# reptolamp.net
KiCad netlist of a schematic drawn in EAGLE
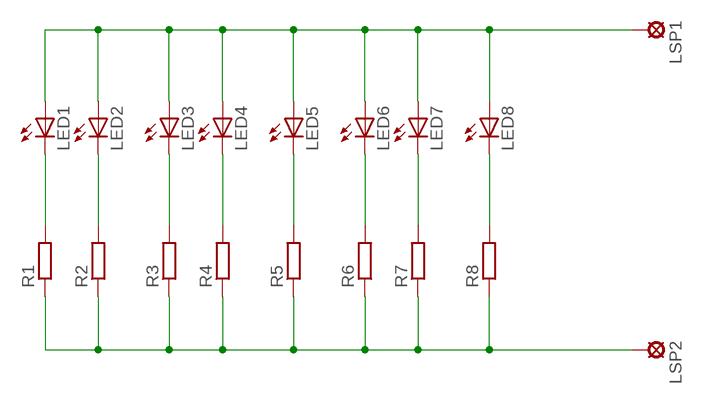
[diagram p0: schematic, sheet 1]

(export (version "E")
  (design (tool "Eeschema 10.0.6"))
  (components
    (comp (ref "LED1")
      (value "LED5MM")
      (footprint "eagle-import:LED5MM")
      (libsource (lib "eagle-import") (part "LED5MM"))
    )
    (comp (ref "LED2")
      (value "LED5MM")
      (footprint "eagle-import:LED5MM")
      (libsource (lib "eagle-import") (part "LED5MM"))
    )
    (comp (ref "LED3")
      (value "LED5MM")
      (footprint "eagle-import:LED5MM")
      (libsource (lib "eagle-import") (part "LED5MM"))
    )
    (comp (ref "LED4")
      (value "LED5MM")
      (footprint "eagle-import:LED5MM")
      (libsource (lib "eagle-import") (part "LED5MM"))
    )
    (comp (ref "LED5")
      (value "LED5MM")
      (footprint "eagle-import:LED5MM")
      (libsource (lib "eagle-import") (part "LED5MM"))
    )
    (comp (ref "LED6")
      (value "LED5MM")
      (footprint "eagle-import:LED5MM")
      (libsource (lib "eagle-import") (part "LED5MM"))
    )
    (comp (ref "LED7")
      (value "LED5MM")
      (footprint "eagle-import:LED5MM")
      (libsource (lib "eagle-import") (part "LED5MM"))
    )
    (comp (ref "LED8")
      (value "LED5MM")
      (footprint "eagle-import:LED5MM")
      (libsource (lib "eagle-import") (part "LED5MM"))
    )
    (comp (ref "LSP1")
      (value "LSP10")
      (footprint "eagle-import:LSP10")
      (libsource (lib "eagle-import") (part "LSP10"))
    )
    (comp (ref "LSP2")
      (value "LSP10")
      (footprint "eagle-import:LSP10")
      (libsource (lib "eagle-import") (part "LSP10"))
    )
    (comp (ref "R1")
      (value "R-EU_0207/10")
      (footprint "eagle-import:0207_10")
      (libsource (lib "eagle-import") (part "R-EU_0207/10"))
    )
    (comp (ref "R2")
      (value "R-EU_0207/10")
      (footprint "eagle-import:0207_10")
      (libsource (lib "eagle-import") (part "R-EU_0207/10"))
    )
    (comp (ref "R3")
      (value "R-EU_0207/10")
      (footprint "eagle-import:0207_10")
      (libsource (lib "eagle-import") (part "R-EU_0207/10"))
    )
    (comp (ref "R4")
      (value "R-EU_0207/10")
      (footprint "eagle-import:0207_10")
      (libsource (lib "eagle-import") (part "R-EU_0207/10"))
    )
    (comp (ref "R5")
      (value "R-EU_0207/10")
      (footprint "eagle-import:0207_10")
      (libsource (lib "eagle-import") (part "R-EU_0207/10"))
    )
    (comp (ref "R6")
      (value "R-EU_0207/10")
      (footprint "eagle-import:0207_10")
      (libsource (lib "eagle-import") (part "R-EU_0207/10"))
    )
    (comp (ref "R7")
      (value "R-EU_0207/10")
      (footprint "eagle-import:0207_10")
      (libsource (lib "eagle-import") (part "R-EU_0207/10"))
    )
    (comp (ref "R8")
      (value "R-EU_0207/10")
      (footprint "eagle-import:0207_10")
      (libsource (lib "eagle-import") (part "R-EU_0207/10"))
    )
  )
  (nets
    (net (code "1") (name "Net-(LED1-C)") (class "Default")
      (node (ref "LED1") (pin "K") (pinfunction "C_K") (pintype "passive"))
      (node (ref "R1") (pin "2") (pinfunction "2_2") (pintype "passive"))
    )
    (net (code "2") (name "Net-(LED1-PadA)") (class "Default")
      (node (ref "LED1") (pin "A") (pinfunction "A_A") (pintype "passive"))
      (node (ref "LED2") (pin "A") (pinfunction "A_A") (pintype "passive"))
      (node (ref "LED3") (pin "A") (pinfunction "A_A") (pintype "passive"))
      (node (ref "LED4") (pin "A") (pinfunction "A_A") (pintype "passive"))
      (node (ref "LED5") (pin "A") (pinfunction "A_A") (pintype "passive"))
      (node (ref "LED6") (pin "A") (pinfunction "A_A") (pintype "passive"))
      (node (ref "LED7") (pin "A") (pinfunction "A_A") (pintype "passive"))
      (node (ref "LED8") (pin "A") (pinfunction "A_A") (pintype "passive"))
      (node (ref "LSP1") (pin "MP") (pinfunction "MP_MP") (pintype "passive"))
    )
    (net (code "3") (name "Net-(LED2-C)") (class "Default")
      (node (ref "LED2") (pin "K") (pinfunction "C_K") (pintype "passive"))
      (node (ref "R2") (pin "2") (pinfunction "2_2") (pintype "passive"))
    )
    (net (code "4") (name "Net-(LED3-C)") (class "Default")
      (node (ref "LED3") (pin "K") (pinfunction "C_K") (pintype "passive"))
      (node (ref "R3") (pin "2") (pinfunction "2_2") (pintype "passive"))
    )
    (net (code "5") (name "Net-(LED4-C)") (class "Default")
      (node (ref "LED4") (pin "K") (pinfunction "C_K") (pintype "passive"))
      (node (ref "R4") (pin "2") (pinfunction "2_2") (pintype "passive"))
    )
    (net (code "6") (name "Net-(LED5-C)") (class "Default")
      (node (ref "LED5") (pin "K") (pinfunction "C_K") (pintype "passive"))
      (node (ref "R5") (pin "2") (pinfunction "2_2") (pintype "passive"))
    )
    (net (code "7") (name "Net-(LED6-C)") (class "Default")
      (node (ref "LED6") (pin "K") (pinfunction "C_K") (pintype "passive"))
      (node (ref "R6") (pin "2") (pinfunction "2_2") (pintype "passive"))
    )
    (net (code "8") (name "Net-(LED7-C)") (class "Default")
      (node (ref "LED7") (pin "K") (pinfunction "C_K") (pintype "passive"))
      (node (ref "R7") (pin "2") (pinfunction "2_2") (pintype "passive"))
    )
    (net (code "9") (name "Net-(LED8-C)") (class "Default")
      (node (ref "LED8") (pin "K") (pinfunction "C_K") (pintype "passive"))
      (node (ref "R8") (pin "2") (pinfunction "2_2") (pintype "passive"))
    )
    (net (code "10") (name "Net-(LSP2-PadMP)") (class "Default")
      (node (ref "LSP2") (pin "MP") (pinfunction "MP_MP") (pintype "passive"))
      (node (ref "R1") (pin "1") (pinfunction "1_1") (pintype "passive"))
      (node (ref "R2") (pin "1") (pinfunction "1_1") (pintype "passive"))
      (node (ref "R3") (pin "1") (pinfunction "1_1") (pintype "passive"))
      (node (ref "R4") (pin "1") (pinfunction "1_1") (pintype "passive"))
      (node (ref "R5") (pin "1") (pinfunction "1_1") (pintype "passive"))
      (node (ref "R6") (pin "1") (pinfunction "1_1") (pintype "passive"))
      (node (ref "R7") (pin "1") (pinfunction "1_1") (pintype "passive"))
      (node (ref "R8") (pin "1") (pinfunction "1_1") (pintype "passive"))
    )
  )
)
